# MCU.net
KiCad netlist of a schematic drawn in Altium Designer
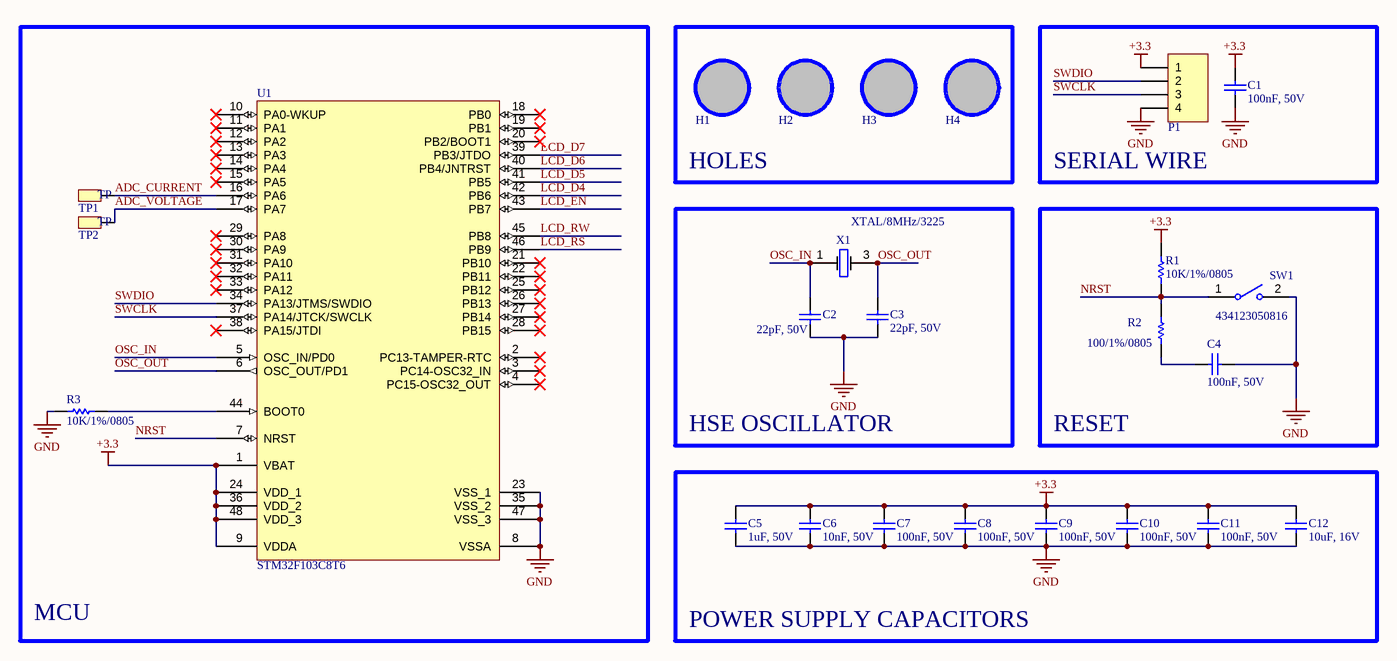
[diagram p0: MCU.SchDoc]

(export (version "E")
  (design (tool "Eeschema 10.0.6"))
  (components
    (comp (ref "C1")
      (value "100nF, 50V")
      (footprint "WCAP-CSGP_0805_H=0.8mm_Wave")
      (description "WCAP-CSGP Multilayer Ceramic Chip Capacitor, General Purpose, size 0805, X7R, 100nF, 50V")
      (fields
        (field (name "MANUFACTURER PART NUMBER") "885012207098")
        (field (name "MANUFACTURER") "Wurth Elektronik")
      )
      (libsource (lib "Altium_WCAP-CSGP (rev20a)") (part "885012207098"))
    )
    (comp (ref "C2")
      (value "22pF, 50V")
      (footprint "WCAP-CSGP_0805_H=0.6mm_Reflow")
      (description "WCAP-CSGP Multilayer Ceramic Chip Capacitor, General Purpose, size 0805, NP0, 22pF, 50V")
      (fields
        (field (name "MANUFACTURER PART NUMBER") "885012007053")
        (field (name "MANUFACTURER") "Wurth Elektronik")
      )
      (libsource (lib "Altium_WCAP-CSGP (rev20a)") (part "885012007053"))
    )
    (comp (ref "C3")
      (value "22pF, 50V")
      (footprint "WCAP-CSGP_0805_H=0.6mm_Reflow")
      (description "WCAP-CSGP Multilayer Ceramic Chip Capacitor, General Purpose, size 0805, NP0, 22pF, 50V")
      (fields
        (field (name "MANUFACTURER PART NUMBER") "885012007053")
        (field (name "MANUFACTURER") "Wurth Elektronik")
      )
      (libsource (lib "Altium_WCAP-CSGP (rev20a)") (part "885012007053"))
    )
    (comp (ref "C4")
      (value "100nF, 50V")
      (footprint "WCAP-CSGP_0805_H=0.8mm_Wave")
      (description "WCAP-CSGP Multilayer Ceramic Chip Capacitor, General Purpose, size 0805, X7R, 100nF, 50V")
      (fields
        (field (name "MANUFACTURER PART NUMBER") "885012207098")
        (field (name "MANUFACTURER") "Wurth Elektronik")
      )
      (libsource (lib "Altium_WCAP-CSGP (rev20a)") (part "885012207098"))
    )
    (comp (ref "C5")
      (value "1uF, 50V")
      (footprint "WCAP-CSGP_0805_H=1.25mm")
      (description "WCAP-CSGP Multilayer Ceramic Chip Capacitor, General Purpose, size 0805, X7R, 1uF, 50V")
      (fields
        (field (name "MANUFACTURER PART NUMBER") "885012207103")
        (field (name "MANUFACTURER") "Wurth Elektronik")
      )
      (libsource (lib "Altium_WCAP-CSGP (rev20a)") (part "885012207103"))
    )
    (comp (ref "C6")
      (value "10nF, 50V")
      (footprint "WCAP-CSGP_0805_H=0.8mm_Reflow")
      (description "WCAP-CSGP Multilayer Ceramic Chip Capacitor, General Purpose, size 0805, X7R, 10nF, 50V")
      (fields
        (field (name "MANUFACTURER PART NUMBER") "885012207092")
        (field (name "MANUFACTURER") "Wurth Elektronik")
      )
      (libsource (lib "Altium_WCAP-CSGP (rev20a)") (part "885012207092"))
    )
    (comp (ref "C7")
      (value "100nF, 50V")
      (footprint "WCAP-CSGP_0805_H=0.8mm_Wave")
      (description "WCAP-CSGP Multilayer Ceramic Chip Capacitor, General Purpose, size 0805, X7R, 100nF, 50V")
      (fields
        (field (name "MANUFACTURER PART NUMBER") "885012207098")
        (field (name "MANUFACTURER") "Wurth Elektronik")
      )
      (libsource (lib "Altium_WCAP-CSGP (rev20a)") (part "885012207098"))
    )
    (comp (ref "C8")
      (value "100nF, 50V")
      (footprint "WCAP-CSGP_0805_H=0.8mm_Wave")
      (description "WCAP-CSGP Multilayer Ceramic Chip Capacitor, General Purpose, size 0805, X7R, 100nF, 50V")
      (fields
        (field (name "MANUFACTURER PART NUMBER") "885012207098")
        (field (name "MANUFACTURER") "Wurth Elektronik")
      )
      (libsource (lib "Altium_WCAP-CSGP (rev20a)") (part "885012207098"))
    )
    (comp (ref "C9")
      (value "100nF, 50V")
      (footprint "WCAP-CSGP_0805_H=0.8mm_Wave")
      (description "WCAP-CSGP Multilayer Ceramic Chip Capacitor, General Purpose, size 0805, X7R, 100nF, 50V")
      (fields
        (field (name "MANUFACTURER PART NUMBER") "885012207098")
        (field (name "MANUFACTURER") "Wurth Elektronik")
      )
      (libsource (lib "Altium_WCAP-CSGP (rev20a)") (part "885012207098"))
    )
    (comp (ref "C10")
      (value "100nF, 50V")
      (footprint "WCAP-CSGP_0805_H=0.8mm_Wave")
      (description "WCAP-CSGP Multilayer Ceramic Chip Capacitor, General Purpose, size 0805, X7R, 100nF, 50V")
      (fields
        (field (name "MANUFACTURER PART NUMBER") "885012207098")
        (field (name "MANUFACTURER") "Wurth Elektronik")
      )
      (libsource (lib "Altium_WCAP-CSGP (rev20a)") (part "885012207098"))
    )
    (comp (ref "C11")
      (value "100nF, 50V")
      (footprint "WCAP-CSGP_0805_H=0.8mm_Wave")
      (description "WCAP-CSGP Multilayer Ceramic Chip Capacitor, General Purpose, size 0805, X7R, 100nF, 50V")
      (fields
        (field (name "MANUFACTURER PART NUMBER") "885012207098")
        (field (name "MANUFACTURER") "Wurth Elektronik")
      )
      (libsource (lib "Altium_WCAP-CSGP (rev20a)") (part "885012207098"))
    )
    (comp (ref "C12")
      (value "10uF, 16V")
      (footprint "WCAP-CSGP_0805_H=1.25mm")
      (description "WCAP-CSGP Multilayer Ceramic Chip Capacitor, General Purpose, size 0805, X5R, 10uF, 16V")
      (fields
        (field (name "MANUFACTURER PART NUMBER") "885012107014")
        (field (name "MANUFACTURER") "Wurth Elektronik")
      )
      (libsource (lib "Altium_WCAP-CSGP (rev20a)") (part "885012107014"))
    )
    (comp (ref "H1")
      (value "Hole")
      (footprint "LO KHOAN 3MM")
      (description "Hole 3mm")
      (libsource (lib "PIF_Library") (part "Hole"))
    )
    (comp (ref "H2")
      (value "Hole")
      (footprint "LO KHOAN 3MM")
      (description "Hole 3mm")
      (libsource (lib "PIF_Library") (part "Hole"))
    )
    (comp (ref "H3")
      (value "Hole")
      (footprint "LO KHOAN 3MM")
      (description "Hole 3mm")
      (libsource (lib "PIF_Library") (part "Hole"))
    )
    (comp (ref "H4")
      (value "Hole")
      (footprint "LO KHOAN 3MM")
      (description "Hole 3mm")
      (libsource (lib "PIF_Library") (part "Hole"))
    )
    (comp (ref "P1")
      (value "Header 4")
      (footprint "JP4")
      (description "Header, 4-Pin")
      (fields (field (name "PUBLISHER") "Altium Limited"))
      (libsource (lib "PIF_Library") (part "Header 4"))
    )
    (comp (ref "R1")
      (value "10K/1%/0805")
      (footprint "RES-SM-0805")
      (description "Resistor")
      (fields (field (name "Comment") "RESISTOR SMD"))
      (libsource (lib "PIF_Library") (part "RESISTOR SMD"))
    )
    (comp (ref "R2")
      (value "100/1%/0805")
      (footprint "RES-SM-0805")
      (description "Resistor")
      (fields (field (name "Comment") "RESISTOR SMD"))
      (libsource (lib "PIF_Library") (part "RESISTOR SMD"))
    )
    (comp (ref "R3")
      (value "10K/1%/0805")
      (footprint "RES-SM-0805")
      (description "Resistor")
      (fields (field (name "Comment") "RESISTOR SMD"))
      (libsource (lib "PIF_Library") (part "RESISTOR SMD"))
    )
    (comp (ref "SW1")
      (value "434123050816")
      (footprint "WS-TASV_L6W3.5H5_4341x30508x6")
      (description "WS-TASV J-Bend SMT Tact Switch, 12VDC, 50mA, 160g, height 5mm")
      (fields (field (name "MANUFACTURER") "Wurth Elektronik"))
      (libsource (lib "Altium_WS-TASV (rev22a)") (part "434123050816"))
    )
    (comp (ref "TP1")
      (value "Test Point")
      (footprint "TP")
      (libsource (lib "PIF_Library") (part "Test Point"))
    )
    (comp (ref "TP2")
      (value "Test Point")
      (footprint "TP")
      (libsource (lib "PIF_Library") (part "Test Point"))
    )
    (comp (ref "U1")
      (value "STM32F103C8T6")
      (footprint "TSQFP50P900X900X160-48N")
      (fields (field (name "MANUFACTURER") "ST"))
      (libsource (lib "MiclsLib") (part "STM32F103C8T6"))
    )
    (comp (ref "X1")
      (value "XTAL/8MHz/3225")
      (footprint "XTAL 3225")
      (libsource (lib "MiclsLib") (part "XTAL"))
    )
  )
  (nets
    (net (code "1") (name "+3.3") (class "Default")
      (node (ref "C1") (pin "1") (pinfunction "1_1") (pintype "passive"))
      (node (ref "C10") (pin "2") (pinfunction "2_2") (pintype "passive"))
      (node (ref "C11") (pin "2") (pinfunction "2_2") (pintype "passive"))
      (node (ref "C12") (pin "2") (pinfunction "2_2") (pintype "passive"))
      (node (ref "C5") (pin "2") (pinfunction "2_2") (pintype "passive"))
      (node (ref "C6") (pin "2") (pinfunction "2_2") (pintype "passive"))
      (node (ref "C7") (pin "2") (pinfunction "2_2") (pintype "passive"))
      (node (ref "C8") (pin "2") (pinfunction "2_2") (pintype "passive"))
      (node (ref "C9") (pin "2") (pinfunction "2_2") (pintype "passive"))
      (node (ref "P1") (pin "1") (pinfunction "1_1") (pintype "passive"))
      (node (ref "R1") (pin "2") (pinfunction "2_2") (pintype "passive"))
      (node (ref "U1") (pin "1") (pinfunction "VBAT_1") (pintype "power_in"))
      (node (ref "U1") (pin "24") (pinfunction "VDD_1_24") (pintype "power_in"))
      (node (ref "U1") (pin "36") (pinfunction "VDD_2_36") (pintype "power_in"))
      (node (ref "U1") (pin "48") (pinfunction "VDD_3_48") (pintype "power_in"))
      (node (ref "U1") (pin "9") (pinfunction "VDDA_9") (pintype "power_in"))
    )
    (net (code "2") (name "/ADC_CURRENT") (class "Default")
      (node (ref "TP1") (pin "TP1") (pinfunction "0_TP1") (pintype "passive"))
      (node (ref "U1") (pin "16") (pinfunction "PA6_16") (pintype "bidirectional"))
    )
    (net (code "3") (name "/ADC_VOLTAGE") (class "Default")
      (node (ref "TP2") (pin "TP1") (pinfunction "0_TP1") (pintype "passive"))
      (node (ref "U1") (pin "17") (pinfunction "PA7_17") (pintype "bidirectional"))
    )
    (net (code "4") (name "/LCD_D4") (class "Default")
      (node (ref "U1") (pin "42") (pinfunction "PB6_42") (pintype "bidirectional"))
    )
    (net (code "5") (name "/LCD_D5") (class "Default")
      (node (ref "U1") (pin "41") (pinfunction "PB5_41") (pintype "bidirectional"))
    )
    (net (code "6") (name "/LCD_D6") (class "Default")
      (node (ref "U1") (pin "40") (pinfunction "PB4/JNTRST_40") (pintype "bidirectional"))
    )
    (net (code "7") (name "/LCD_D7") (class "Default")
      (node (ref "U1") (pin "39") (pinfunction "PB3/JTDO_39") (pintype "bidirectional"))
    )
    (net (code "8") (name "/LCD_EN") (class "Default")
      (node (ref "U1") (pin "43") (pinfunction "PB7_43") (pintype "bidirectional"))
    )
    (net (code "9") (name "/LCD_RS") (class "Default")
      (node (ref "U1") (pin "46") (pinfunction "PB9_46") (pintype "bidirectional"))
    )
    (net (code "10") (name "/LCD_RW") (class "Default")
      (node (ref "U1") (pin "45") (pinfunction "PB8_45") (pintype "bidirectional"))
    )
    (net (code "11") (name "/NRST") (class "Default")
      (node (ref "R1") (pin "1") (pinfunction "1_1") (pintype "passive"))
      (node (ref "R2") (pin "2") (pinfunction "2_2") (pintype "passive"))
      (node (ref "SW1") (pin "1") (pinfunction "1_1") (pintype "passive"))
      (node (ref "U1") (pin "7") (pinfunction "NRST_7") (pintype "bidirectional"))
    )
    (net (code "12") (name "/OSC_IN") (class "Default")
      (node (ref "C2") (pin "2") (pinfunction "2_2") (pintype "passive"))
      (node (ref "U1") (pin "5") (pinfunction "OSC_IN/PD0_5") (pintype "input"))
      (node (ref "X1") (pin "1") (pinfunction "8_1") (pintype "passive"))
    )
    (net (code "13") (name "/OSC_OUT") (class "Default")
      (node (ref "C3") (pin "2") (pinfunction "2_2") (pintype "passive"))
      (node (ref "U1") (pin "6") (pinfunction "OSC_OUT/PD1_6") (pintype "output"))
      (node (ref "X1") (pin "3") (pinfunction "9_3") (pintype "passive"))
    )
    (net (code "14") (name "/SWCLK") (class "Default")
      (node (ref "P1") (pin "3") (pinfunction "3_3") (pintype "passive"))
      (node (ref "U1") (pin "37") (pinfunction "PA14/JTCK/SWCLK_37") (pintype "bidirectional"))
    )
    (net (code "15") (name "/SWDIO") (class "Default")
      (node (ref "P1") (pin "2") (pinfunction "2_2") (pintype "passive"))
      (node (ref "U1") (pin "34") (pinfunction "PA13/JTMS/SWDIO_34") (pintype "bidirectional"))
    )
    (net (code "16") (name "GND") (class "Default")
      (node (ref "C1") (pin "2") (pinfunction "2_2") (pintype "passive"))
      (node (ref "C10") (pin "1") (pinfunction "1_1") (pintype "passive"))
      (node (ref "C11") (pin "1") (pinfunction "1_1") (pintype "passive"))
      (node (ref "C12") (pin "1") (pinfunction "1_1") (pintype "passive"))
      (node (ref "C2") (pin "1") (pinfunction "1_1") (pintype "passive"))
      (node (ref "C3") (pin "1") (pinfunction "1_1") (pintype "passive"))
      (node (ref "C4") (pin "1") (pinfunction "1_1") (pintype "passive"))
      (node (ref "C5") (pin "1") (pinfunction "1_1") (pintype "passive"))
      (node (ref "C6") (pin "1") (pinfunction "1_1") (pintype "passive"))
      (node (ref "C7") (pin "1") (pinfunction "1_1") (pintype "passive"))
      (node (ref "C8") (pin "1") (pinfunction "1_1") (pintype "passive"))
      (node (ref "C9") (pin "1") (pinfunction "1_1") (pintype "passive"))
      (node (ref "P1") (pin "4") (pinfunction "4_4") (pintype "passive"))
      (node (ref "R3") (pin "2") (pinfunction "2_2") (pintype "passive"))
      (node (ref "SW1") (pin "2") (pinfunction "2_2") (pintype "passive"))
      (node (ref "U1") (pin "23") (pinfunction "VSS_1_23") (pintype "power_in"))
      (node (ref "U1") (pin "35") (pinfunction "VSS_2_35") (pintype "power_in"))
      (node (ref "U1") (pin "47") (pinfunction "VSS_3_47") (pintype "power_in"))
      (node (ref "U1") (pin "8") (pinfunction "VSSA_8") (pintype "power_in"))
    )
    (net (code "17") (name "Net-(C4-Pad2)") (class "Default")
      (node (ref "C4") (pin "2") (pinfunction "2_2") (pintype "passive"))
      (node (ref "R2") (pin "1") (pinfunction "1_1") (pintype "passive"))
    )
    (net (code "18") (name "Net-(U1-BOOT0)") (class "Default")
      (node (ref "R3") (pin "1") (pinfunction "1_1") (pintype "passive"))
      (node (ref "U1") (pin "44") (pinfunction "BOOT0_44") (pintype "input"))
    )
    (net (code "19") (name "unconnected-(H1-Pad1)") (class "Default")
      (node (ref "H1") (pin "1") (pinfunction "1_1") (pintype "passive"))
    )
    (net (code "20") (name "unconnected-(H2-Pad1)") (class "Default")
      (node (ref "H2") (pin "1") (pinfunction "1_1") (pintype "passive"))
    )
    (net (code "21") (name "unconnected-(H3-Pad1)") (class "Default")
      (node (ref "H3") (pin "1") (pinfunction "1_1") (pintype "passive"))
    )
    (net (code "22") (name "unconnected-(H4-Pad1)") (class "Default")
      (node (ref "H4") (pin "1") (pinfunction "1_1") (pintype "passive"))
    )
    (net (code "23") (name "unconnected-(U1-PA0-WKUP-Pad10)") (class "Default")
      (node (ref "U1") (pin "10") (pinfunction "PA0-WKUP_10") (pintype "bidirectional+no_connect"))
    )
    (net (code "24") (name "unconnected-(U1-PA1-Pad11)") (class "Default")
      (node (ref "U1") (pin "11") (pinfunction "PA1_11") (pintype "bidirectional+no_connect"))
    )
    (net (code "25") (name "unconnected-(U1-PA2-Pad12)") (class "Default")
      (node (ref "U1") (pin "12") (pinfunction "PA2_12") (pintype "bidirectional+no_connect"))
    )
    (net (code "26") (name "unconnected-(U1-PA3-Pad13)") (class "Default")
      (node (ref "U1") (pin "13") (pinfunction "PA3_13") (pintype "bidirectional+no_connect"))
    )
    (net (code "27") (name "unconnected-(U1-PA4-Pad14)") (class "Default")
      (node (ref "U1") (pin "14") (pinfunction "PA4_14") (pintype "bidirectional+no_connect"))
    )
    (net (code "28") (name "unconnected-(U1-PA5-Pad15)") (class "Default")
      (node (ref "U1") (pin "15") (pinfunction "PA5_15") (pintype "bidirectional+no_connect"))
    )
    (net (code "29") (name "unconnected-(U1-PA8-Pad29)") (class "Default")
      (node (ref "U1") (pin "29") (pinfunction "PA8_29") (pintype "bidirectional+no_connect"))
    )
    (net (code "30") (name "unconnected-(U1-PA9-Pad30)") (class "Default")
      (node (ref "U1") (pin "30") (pinfunction "PA9_30") (pintype "bidirectional+no_connect"))
    )
    (net (code "31") (name "unconnected-(U1-PA10-Pad31)") (class "Default")
      (node (ref "U1") (pin "31") (pinfunction "PA10_31") (pintype "bidirectional+no_connect"))
    )
    (net (code "32") (name "unconnected-(U1-PA11-Pad32)") (class "Default")
      (node (ref "U1") (pin "32") (pinfunction "PA11_32") (pintype "bidirectional+no_connect"))
    )
    (net (code "33") (name "unconnected-(U1-PA12-Pad33)") (class "Default")
      (node (ref "U1") (pin "33") (pinfunction "PA12_33") (pintype "bidirectional+no_connect"))
    )
    (net (code "34") (name "unconnected-(U1-PA15{slash}JTDI-Pad38)") (class "Default")
      (node (ref "U1") (pin "38") (pinfunction "PA15/JTDI_38") (pintype "bidirectional+no_connect"))
    )
    (net (code "35") (name "unconnected-(U1-PB0-Pad18)") (class "Default")
      (node (ref "U1") (pin "18") (pinfunction "PB0_18") (pintype "bidirectional+no_connect"))
    )
    (net (code "36") (name "unconnected-(U1-PB1-Pad19)") (class "Default")
      (node (ref "U1") (pin "19") (pinfunction "PB1_19") (pintype "bidirectional+no_connect"))
    )
    (net (code "37") (name "unconnected-(U1-PB2{slash}BOOT1-Pad20)") (class "Default")
      (node (ref "U1") (pin "20") (pinfunction "PB2/BOOT1_20") (pintype "bidirectional+no_connect"))
    )
    (net (code "38") (name "unconnected-(U1-PB10-Pad21)") (class "Default")
      (node (ref "U1") (pin "21") (pinfunction "PB10_21") (pintype "bidirectional+no_connect"))
    )
    (net (code "39") (name "unconnected-(U1-PB11-Pad22)") (class "Default")
      (node (ref "U1") (pin "22") (pinfunction "PB11_22") (pintype "bidirectional+no_connect"))
    )
    (net (code "40") (name "unconnected-(U1-PB12-Pad25)") (class "Default")
      (node (ref "U1") (pin "25") (pinfunction "PB12_25") (pintype "bidirectional+no_connect"))
    )
    (net (code "41") (name "unconnected-(U1-PB13-Pad26)") (class "Default")
      (node (ref "U1") (pin "26") (pinfunction "PB13_26") (pintype "bidirectional+no_connect"))
    )
    (net (code "42") (name "unconnected-(U1-PB14-Pad27)") (class "Default")
      (node (ref "U1") (pin "27") (pinfunction "PB14_27") (pintype "bidirectional+no_connect"))
    )
    (net (code "43") (name "unconnected-(U1-PB15-Pad28)") (class "Default")
      (node (ref "U1") (pin "28") (pinfunction "PB15_28") (pintype "bidirectional+no_connect"))
    )
    (net (code "44") (name "unconnected-(U1-PC13-TAMPER-RTC-Pad2)") (class "Default")
      (node (ref "U1") (pin "2") (pinfunction "PC13-TAMPER-RTC_2") (pintype "bidirectional+no_connect"))
    )
    (net (code "45") (name "unconnected-(U1-PC14-OSC32_IN-Pad3)") (class "Default")
      (node (ref "U1") (pin "3") (pinfunction "PC14-OSC32_IN_3") (pintype "bidirectional+no_connect"))
    )
    (net (code "46") (name "unconnected-(U1-PC15-OSC32_OUT-Pad4)") (class "Default")
      (node (ref "U1") (pin "4") (pinfunction "PC15-OSC32_OUT_4") (pintype "bidirectional+no_connect"))
    )
  )
)
